# ADC_DAC_channel.net
KiCad netlist of a schematic drawn in Altium Designer
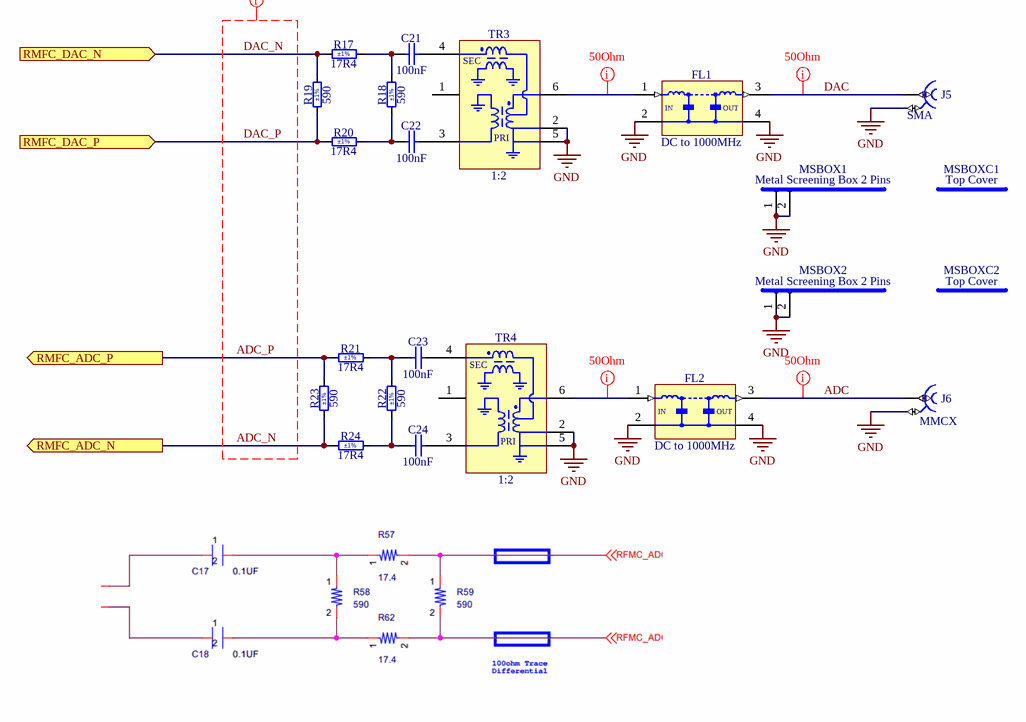
[diagram p0: ADC_DAC_channel.SchDoc]

(export (version "E")
  (design (tool "Eeschema 10.0.6"))
  (components
    (comp (ref "C21")
      (value "100nF")
      (footprint "CAPC1005X55N")
      (description "Non-polarised capacitor")
      (fields
        (field (name "PART NUMBER") "CC0402_100NF_16V_10%_X5R")
        (field (name "VOLTAGE") "16V")
        (field (name "AUTHOR") "CERN DEM JLC")
      )
      (libsource (lib "Capacitors") (part "Capacitor - non polarized"))
    )
    (comp (ref "C22")
      (value "100nF")
      (footprint "CAPC1005X55N")
      (description "Non-polarised capacitor")
      (fields
        (field (name "PART NUMBER") "CC0402_100NF_16V_10%_X5R")
        (field (name "VOLTAGE") "16V")
        (field (name "AUTHOR") "CERN DEM JLC")
      )
      (libsource (lib "Capacitors") (part "Capacitor - non polarized"))
    )
    (comp (ref "C23")
      (value "100nF")
      (footprint "CAPC1005X55N")
      (description "Non-polarised capacitor")
      (fields
        (field (name "PART NUMBER") "CC0402_100NF_16V_10%_X5R")
        (field (name "VOLTAGE") "16V")
        (field (name "AUTHOR") "CERN DEM JLC")
      )
      (libsource (lib "Capacitors") (part "Capacitor - non polarized"))
    )
    (comp (ref "C24")
      (value "100nF")
      (footprint "CAPC1005X55N")
      (description "Non-polarised capacitor")
      (fields
        (field (name "PART NUMBER") "CC0402_100NF_16V_10%_X5R")
        (field (name "VOLTAGE") "16V")
        (field (name "AUTHOR") "CERN DEM JLC")
      )
      (libsource (lib "Capacitors") (part "Capacitor - non polarized"))
    )
    (comp (ref "FL1")
      (value "DC to 1000MHz")
      (footprint "FIL_MINI-CIRCUITS_FV1206")
      (description "50 Ohm Low Pass Filter")
      (fields
        (field (name "PART NUMBER") "FIL_MINI-CIRCUITS_LFCN-1000+")
        (field (name "MANUFACTURER") "MINI-CIRCUITS")
        (field (name "AUTHOR") "CERN DEM MR")
      )
      (libsource (lib "Inductors & Transformers") (part "FIL_MINI-CIRCUITS_LFCN"))
    )
    (comp (ref "FL2")
      (value "DC to 1000MHz")
      (footprint "FIL_MINI-CIRCUITS_FV1206")
      (description "50 Ohm Low Pass Filter")
      (fields
        (field (name "PART NUMBER") "FIL_MINI-CIRCUITS_LFCN-1000+")
        (field (name "MANUFACTURER") "MINI-CIRCUITS")
        (field (name "AUTHOR") "CERN DEM MR")
      )
      (libsource (lib "Inductors & Transformers") (part "FIL_MINI-CIRCUITS_LFCN"))
    )
    (comp (ref "J5")
      (value "SMA")
      (footprint "TELEGARTNER_J01151A0451")
      (fields
        (field (name "PART NUMBER") "TELEGARTNER_J01151A0451")
        (field (name "MANUFACTURER") "TELEGARTNER")
        (field (name "MANUFACTURER PART NUMBER") "J01151A0451")
        (field (name "AUTHOR") "CERN DEM JLC")
      )
      (libsource (lib "Connectors") (part "Coax_1Female_1Shield"))
    )
    (comp (ref "J6")
      (value "Coax_1Female_1Shield")
      (footprint "HUBER-SUHNER_85_MMCX-50-0-1/111_OE")
      (fields
        (field (name "PART NUMBER") "HUBER-SUHNER_85_MMCX-50-0-1/111_OE")
        (field (name "FAMILY") "MMCX")
        (field (name "MANUFACTURER") "HUBER+SUHNER")
        (field (name "MANUFACTURER PART NUMBER") "85_MMCX-50-0-1/111_OE")
        (field (name "AUTHOR") "CERN DEM JLC")
      )
      (libsource (lib "Connectors") (part "Coax_1Female_1Shield"))
    )
    (comp (ref "MSBOX1")
      (value "Metal Screening Box 2 Pins")
      (footprint "MSBOX_WURTH_3670130")
      (fields
        (field (name "PART NUMBER") "MSBOX_WURTH_3670130")
        (field (name "MANUFACTURER") "WURTH")
        (field (name "MANUFACTURER PART NUMBER") "3670130")
        (field (name "AUTHOR") "CERN DEM BC")
      )
      (libsource (lib "Eletro-mechanical") (part "Metal Screening Box - 2 pins"))
    )
    (comp (ref "MSBOX2")
      (value "Metal Screening Box 2 Pins")
      (footprint "MSBOX_WURTH_3670130")
      (fields
        (field (name "PART NUMBER") "MSBOX_WURTH_3670130")
        (field (name "MANUFACTURER") "WURTH")
        (field (name "MANUFACTURER PART NUMBER") "3670130")
        (field (name "AUTHOR") "CERN DEM BC")
      )
      (libsource (lib "Eletro-mechanical") (part "Metal Screening Box - 2 pins"))
    )
    (comp (ref "MSBOXC1")
      (value "Top Cover")
      (footprint "MSBOX_WURTH_3671130")
      (description "Metal Screening Box - Top Cover 0 Pin")
      (fields
        (field (name "PART NUMBER") "MSBOX_WURTH_3671130")
        (field (name "MANUFACTURER") "WURTH")
        (field (name "AUTHOR") "CERN DEM BC")
      )
      (libsource (lib "Eletro-mechanical") (part "Metal Screening Box - Top Cover"))
    )
    (comp (ref "MSBOXC2")
      (value "Top Cover")
      (footprint "MSBOX_WURTH_3671130")
      (description "Metal Screening Box - Top Cover 0 Pin")
      (fields
        (field (name "PART NUMBER") "MSBOX_WURTH_3671130")
        (field (name "MANUFACTURER") "WURTH")
        (field (name "AUTHOR") "CERN DEM BC")
      )
      (libsource (lib "Eletro-mechanical") (part "Metal Screening Box - Top Cover"))
    )
    (comp (ref "R17")
      (value "17R4")
      (footprint "RESC1005X40N")
      (description "Resistor - 1%")
      (fields
        (field (name "TOLERANCE") "±1%")
        (field (name "PART NUMBER") "R0402_17R4_1%_0.1W_100PPM")
        (field (name "POWER") "0.1W")
        (field (name "AUTHOR") "CERN DEM BC")
      )
      (libsource (lib "Resistors") (part "Resistor - 1%"))
    )
    (comp (ref "R18")
      (value "590")
      (footprint "RESC1005X40N")
      (description "Resistor - 1%")
      (fields
        (field (name "TOLERANCE") "±1%")
        (field (name "PART NUMBER") "R0402_590R_1%_0.1W_100PPM")
        (field (name "POWER") "0.1W")
        (field (name "AUTHOR") "CERN DEM BC")
      )
      (libsource (lib "Resistors") (part "Resistor - 1%"))
    )
    (comp (ref "R19")
      (value "590")
      (footprint "RESC1005X40N")
      (description "Resistor - 1%")
      (fields
        (field (name "TOLERANCE") "±1%")
        (field (name "PART NUMBER") "R0402_590R_1%_0.1W_100PPM")
        (field (name "POWER") "0.1W")
        (field (name "AUTHOR") "CERN DEM BC")
      )
      (libsource (lib "Resistors") (part "Resistor - 1%"))
    )
    (comp (ref "R20")
      (value "17R4")
      (footprint "RESC1005X40N")
      (description "Resistor - 1%")
      (fields
        (field (name "TOLERANCE") "±1%")
        (field (name "PART NUMBER") "R0402_17R4_1%_0.1W_100PPM")
        (field (name "POWER") "0.1W")
        (field (name "AUTHOR") "CERN DEM BC")
      )
      (libsource (lib "Resistors") (part "Resistor - 1%"))
    )
    (comp (ref "R21")
      (value "17R4")
      (footprint "RESC1005X40N")
      (description "Resistor - 1%")
      (fields
        (field (name "TOLERANCE") "±1%")
        (field (name "PART NUMBER") "R0402_17R4_1%_0.1W_100PPM")
        (field (name "POWER") "0.1W")
        (field (name "AUTHOR") "CERN DEM BC")
      )
      (libsource (lib "Resistors") (part "Resistor - 1%"))
    )
    (comp (ref "R22")
      (value "590")
      (footprint "RESC1005X40N")
      (description "Resistor - 1%")
      (fields
        (field (name "TOLERANCE") "±1%")
        (field (name "PART NUMBER") "R0402_590R_1%_0.1W_100PPM")
        (field (name "POWER") "0.1W")
        (field (name "AUTHOR") "CERN DEM BC")
      )
      (libsource (lib "Resistors") (part "Resistor - 1%"))
    )
    (comp (ref "R23")
      (value "590")
      (footprint "RESC1005X40N")
      (description "Resistor - 1%")
      (fields
        (field (name "TOLERANCE") "±1%")
        (field (name "PART NUMBER") "R0402_590R_1%_0.1W_100PPM")
        (field (name "POWER") "0.1W")
        (field (name "AUTHOR") "CERN DEM BC")
      )
      (libsource (lib "Resistors") (part "Resistor - 1%"))
    )
    (comp (ref "R24")
      (value "17R4")
      (footprint "RESC1005X40N")
      (description "Resistor - 1%")
      (fields
        (field (name "TOLERANCE") "±1%")
        (field (name "PART NUMBER") "R0402_17R4_1%_0.1W_100PPM")
        (field (name "POWER") "0.1W")
        (field (name "AUTHOR") "CERN DEM BC")
      )
      (libsource (lib "Resistors") (part "Resistor - 1%"))
    )
    (comp (ref "TR3")
      (value "1:2")
      (footprint "XFMR_MINI-CIRCUITS_DB1627")
      (description "50 OHMS 10 to 3000 MHz RF Transformer")
      (fields
        (field (name "PART NUMBER") "XFMR_MINI-CIRCUITS_TCM2-33WX+")
        (field (name "POWER") "0.4W")
        (field (name "AUTHOR") "CERN DEM MR")
      )
      (libsource (lib "Inductors & Transformers") (part "XFMR_MINI-CIRCUITS_TCM2-33WX+"))
    )
    (comp (ref "TR4")
      (value "1:2")
      (footprint "XFMR_MINI-CIRCUITS_DB1627")
      (description "50 OHMS 10 to 3000 MHz RF Transformer")
      (fields
        (field (name "PART NUMBER") "XFMR_MINI-CIRCUITS_TCM2-33WX+")
        (field (name "POWER") "0.4W")
        (field (name "AUTHOR") "CERN DEM MR")
      )
      (libsource (lib "Inductors & Transformers") (part "XFMR_MINI-CIRCUITS_TCM2-33WX+"))
    )
  )
  (nets
    (net (code "1") (name "/ADC") (class "Default")
      (node (ref "FL2") (pin "3") (pinfunction "RFOUT_3") (pintype "output"))
      (node (ref "J6") (pin "1") (pinfunction "1_1") (pintype "bidirectional"))
    )
    (net (code "2") (name "/ADC_N") (class "Default")
      (node (ref "R23") (pin "1") (pinfunction "1_1") (pintype "passive"))
      (node (ref "R24") (pin "1") (pinfunction "1_1") (pintype "passive"))
    )
    (net (code "3") (name "/ADC_P") (class "Default")
      (node (ref "R21") (pin "1") (pinfunction "1_1") (pintype "passive"))
      (node (ref "R23") (pin "2") (pinfunction "2_2") (pintype "passive"))
    )
    (net (code "4") (name "/DAC") (class "Default")
      (node (ref "FL1") (pin "3") (pinfunction "RFOUT_3") (pintype "output"))
      (node (ref "J5") (pin "1") (pinfunction "1_1") (pintype "bidirectional"))
    )
    (net (code "5") (name "/DAC_N") (class "Default")
      (node (ref "R17") (pin "1") (pinfunction "1_1") (pintype "passive"))
      (node (ref "R19") (pin "2") (pinfunction "2_2") (pintype "passive"))
    )
    (net (code "6") (name "/DAC_P") (class "Default")
      (node (ref "R19") (pin "1") (pinfunction "1_1") (pintype "passive"))
      (node (ref "R20") (pin "1") (pinfunction "1_1") (pintype "passive"))
    )
    (net (code "7") (name "GND") (class "Default")
      (node (ref "FL1") (pin "2") (pinfunction "GND_2") (pintype "power_in"))
      (node (ref "FL1") (pin "4") (pinfunction "GND_4") (pintype "power_in"))
      (node (ref "FL2") (pin "2") (pinfunction "GND_2") (pintype "power_in"))
      (node (ref "FL2") (pin "4") (pinfunction "GND_4") (pintype "power_in"))
      (node (ref "J5") (pin "2") (pinfunction "2_2") (pintype "bidirectional"))
      (node (ref "J6") (pin "2") (pinfunction "2_2") (pintype "bidirectional"))
      (node (ref "MSBOX1") (pin "1") (pinfunction "1_1") (pintype "passive"))
      (node (ref "MSBOX1") (pin "2") (pinfunction "2_2") (pintype "passive"))
      (node (ref "MSBOX2") (pin "1") (pinfunction "1_1") (pintype "passive"))
      (node (ref "MSBOX2") (pin "2") (pinfunction "2_2") (pintype "passive"))
      (node (ref "TR3") (pin "2") (pinfunction "P_2") (pintype "passive"))
      (node (ref "TR3") (pin "5") (pinfunction "GND_5") (pintype "power_in"))
      (node (ref "TR4") (pin "2") (pinfunction "P_2") (pintype "passive"))
      (node (ref "TR4") (pin "5") (pinfunction "GND_5") (pintype "power_in"))
    )
    (net (code "8") (name "Net-(C21-Pad1)") (class "Default")
      (node (ref "C21") (pin "1") (pinfunction "1_1") (pintype "passive"))
      (node (ref "R17") (pin "2") (pinfunction "2_2") (pintype "passive"))
      (node (ref "R18") (pin "2") (pinfunction "2_2") (pintype "passive"))
    )
    (net (code "9") (name "Net-(C22-Pad1)") (class "Default")
      (node (ref "C22") (pin "1") (pinfunction "1_1") (pintype "passive"))
      (node (ref "R18") (pin "1") (pinfunction "1_1") (pintype "passive"))
      (node (ref "R20") (pin "2") (pinfunction "2_2") (pintype "passive"))
    )
    (net (code "10") (name "Net-(C23-Pad1)") (class "Default")
      (node (ref "C23") (pin "1") (pinfunction "1_1") (pintype "passive"))
      (node (ref "R21") (pin "2") (pinfunction "2_2") (pintype "passive"))
      (node (ref "R22") (pin "2") (pinfunction "2_2") (pintype "passive"))
    )
    (net (code "11") (name "Net-(C24-Pad1)") (class "Default")
      (node (ref "C24") (pin "1") (pinfunction "1_1") (pintype "passive"))
      (node (ref "R22") (pin "1") (pinfunction "1_1") (pintype "passive"))
      (node (ref "R24") (pin "2") (pinfunction "2_2") (pintype "passive"))
    )
    (net (code "12") (name "Net-(FL1-RFIN)") (class "Default")
      (node (ref "FL1") (pin "1") (pinfunction "RFIN_1") (pintype "input"))
      (node (ref "TR3") (pin "6") (pinfunction "P1_6") (pintype "passive"))
    )
    (net (code "13") (name "Net-(FL2-RFIN)") (class "Default")
      (node (ref "FL2") (pin "1") (pinfunction "RFIN_1") (pintype "input"))
      (node (ref "TR4") (pin "6") (pinfunction "P1_6") (pintype "passive"))
    )
    (net (code "14") (name "Net-(TR3-S)") (class "Default")
      (node (ref "C22") (pin "2") (pinfunction "2_2") (pintype "passive"))
      (node (ref "TR3") (pin "3") (pinfunction "S_3") (pintype "passive"))
    )
    (net (code "15") (name "Net-(TR3-SD)") (class "Default")
      (node (ref "C21") (pin "2") (pinfunction "2_2") (pintype "passive"))
      (node (ref "TR3") (pin "4") (pinfunction "SD_4") (pintype "passive"))
    )
    (net (code "16") (name "Net-(TR4-S)") (class "Default")
      (node (ref "C24") (pin "2") (pinfunction "2_2") (pintype "passive"))
      (node (ref "TR4") (pin "3") (pinfunction "S_3") (pintype "passive"))
    )
    (net (code "17") (name "Net-(TR4-SD)") (class "Default")
      (node (ref "C23") (pin "2") (pinfunction "2_2") (pintype "passive"))
      (node (ref "TR4") (pin "4") (pinfunction "SD_4") (pintype "passive"))
    )
    (net (code "18") (name "unconnected-(TR3-NC-Pad1)") (class "Default")
      (node (ref "TR3") (pin "1") (pinfunction "NC_1") (pintype "passive"))
    )
    (net (code "19") (name "unconnected-(TR4-NC-Pad1)") (class "Default")
      (node (ref "TR4") (pin "1") (pinfunction "NC_1") (pintype "passive"))
    )
  )
)
